# KS0108_2Wire.net
KiCad netlist of a schematic drawn in EAGLE
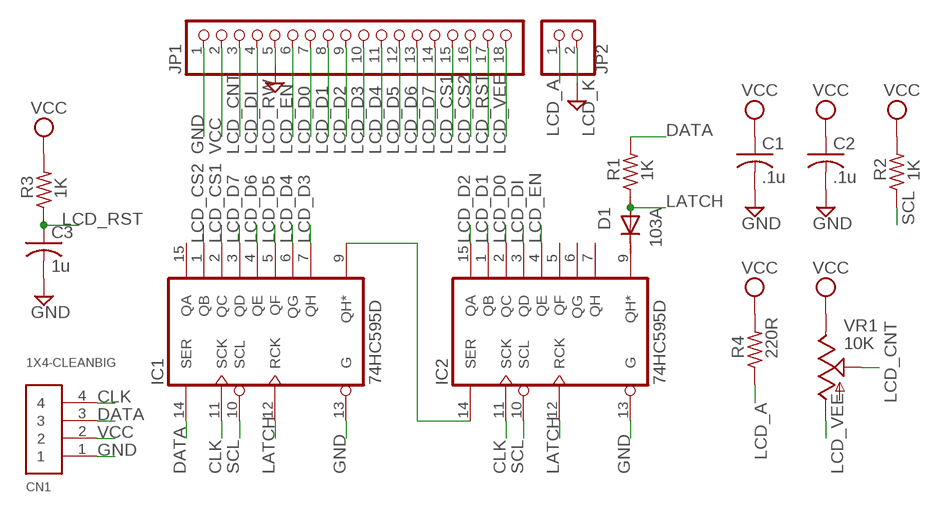
[diagram p0: schematic, sheet 1]

(export (version "E")
  (design (tool "Eeschema 10.0.6"))
  (components
    (comp (ref "C1")
      (value ".1u")
      (footprint "eagle-import:C1206")
      (libsource (lib "eagle-import") (part "C-USC1206"))
    )
    (comp (ref "C2")
      (value ".1u")
      (footprint "eagle-import:C1206")
      (libsource (lib "eagle-import") (part "C-USC1206"))
    )
    (comp (ref "C3")
      (value "1u")
      (footprint "eagle-import:C1206")
      (libsource (lib "eagle-import") (part "C-USC1206"))
    )
    (comp (ref "CN1")
      (value "1X4-CLEANBIG")
      (footprint "eagle-import:1X04-CLEANBIG")
      (libsource (lib "eagle-import") (part "1X4-CLEANBIG"))
    )
    (comp (ref "D1")
      (value "103A")
      (footprint "eagle-import:SOD80C")
      (libsource (lib "eagle-import") (part "DIODE-SOD80C"))
    )
    (comp (ref "IC1")
      (value "74HC595D")
      (footprint "eagle-import:SO16")
      (libsource (lib "eagle-import") (part "74595DHC"))
    )
    (comp (ref "IC2")
      (value "74HC595D")
      (footprint "eagle-import:SO16")
      (libsource (lib "eagle-import") (part "74595DHC"))
    )
    (comp (ref "JP1")
      (value "PINHD-1X18-BIG")
      (footprint "eagle-import:1X18-BIG")
      (libsource (lib "eagle-import") (part "PINHD-1X18-BIG"))
    )
    (comp (ref "JP2")
      (value "HEADER-1X2ROUND")
      (footprint "eagle-import:1X02_ROUND")
      (libsource (lib "eagle-import") (part "HEADER-1X2ROUND"))
    )
    (comp (ref "R1")
      (value "1K")
      (footprint "eagle-import:R1206")
      (libsource (lib "eagle-import") (part "R-US_R1206"))
    )
    (comp (ref "R2")
      (value "1K")
      (footprint "eagle-import:R1206")
      (libsource (lib "eagle-import") (part "R-US_R1206"))
    )
    (comp (ref "R3")
      (value "1K")
      (footprint "eagle-import:R1206")
      (libsource (lib "eagle-import") (part "R-US_R1206"))
    )
    (comp (ref "R4")
      (value "220R")
      (footprint "eagle-import:R1206")
      (libsource (lib "eagle-import") (part "R-US_R1206"))
    )
    (comp (ref "VR1")
      (value "10K")
      (footprint "eagle-import:CT6")
      (libsource (lib "eagle-import") (part "TRIM_US-CT6"))
    )
  )
  (nets
    (net (code "1") (name "/CLK") (class "Default")
      (node (ref "CN1") (pin "4") (pinfunction "4_4") (pintype "bidirectional"))
      (node (ref "IC1") (pin "11") (pinfunction "SCK_11") (pintype "input"))
      (node (ref "IC2") (pin "11") (pinfunction "SCK_11") (pintype "input"))
    )
    (net (code "2") (name "/DATA") (class "Default")
      (node (ref "CN1") (pin "3") (pinfunction "3_3") (pintype "bidirectional"))
      (node (ref "IC1") (pin "14") (pinfunction "SER_14") (pintype "input"))
      (node (ref "R1") (pin "2") (pinfunction "2_2") (pintype "passive"))
    )
    (net (code "3") (name "/LATCH") (class "Default")
      (node (ref "D1") (pin "A") (pinfunction "A_A") (pintype "passive"))
      (node (ref "IC1") (pin "12") (pinfunction "RCK_12") (pintype "input"))
      (node (ref "IC2") (pin "12") (pinfunction "RCK_12") (pintype "input"))
      (node (ref "R1") (pin "1") (pinfunction "1_1") (pintype "passive"))
    )
    (net (code "4") (name "/LCD_A") (class "Default")
      (node (ref "JP2") (pin "1") (pinfunction "1_1") (pintype "passive"))
      (node (ref "R4") (pin "1") (pinfunction "1_1") (pintype "passive"))
    )
    (net (code "5") (name "/LCD_CNT") (class "Default")
      (node (ref "JP1") (pin "3") (pinfunction "3_3") (pintype "passive"))
      (node (ref "VR1") (pin "S") (pinfunction "S_S") (pintype "passive"))
    )
    (net (code "6") (name "/LCD_CS1") (class "Default")
      (node (ref "IC1") (pin "2") (pinfunction "QC_2") (pintype "tri_state"))
      (node (ref "JP1") (pin "15") (pinfunction "15_15") (pintype "passive"))
    )
    (net (code "7") (name "/LCD_CS2") (class "Default")
      (node (ref "IC1") (pin "1") (pinfunction "QB_1") (pintype "tri_state"))
      (node (ref "JP1") (pin "16") (pinfunction "16_16") (pintype "passive"))
    )
    (net (code "8") (name "/LCD_D0") (class "Default")
      (node (ref "IC2") (pin "2") (pinfunction "QC_2") (pintype "tri_state"))
      (node (ref "JP1") (pin "7") (pinfunction "7_7") (pintype "passive"))
    )
    (net (code "9") (name "/LCD_D1") (class "Default")
      (node (ref "IC2") (pin "1") (pinfunction "QB_1") (pintype "tri_state"))
      (node (ref "JP1") (pin "8") (pinfunction "8_8") (pintype "passive"))
    )
    (net (code "10") (name "/LCD_D2") (class "Default")
      (node (ref "IC2") (pin "15") (pinfunction "QA_15") (pintype "tri_state"))
      (node (ref "JP1") (pin "9") (pinfunction "9_9") (pintype "passive"))
    )
    (net (code "11") (name "/LCD_D3") (class "Default")
      (node (ref "IC1") (pin "7") (pinfunction "QH_7") (pintype "tri_state"))
      (node (ref "JP1") (pin "10") (pinfunction "10_10") (pintype "passive"))
    )
    (net (code "12") (name "/LCD_D4") (class "Default")
      (node (ref "IC1") (pin "6") (pinfunction "QG_6") (pintype "tri_state"))
      (node (ref "JP1") (pin "11") (pinfunction "11_11") (pintype "passive"))
    )
    (net (code "13") (name "/LCD_D5") (class "Default")
      (node (ref "IC1") (pin "5") (pinfunction "QF_5") (pintype "tri_state"))
      (node (ref "JP1") (pin "12") (pinfunction "12_12") (pintype "passive"))
    )
    (net (code "14") (name "/LCD_D6") (class "Default")
      (node (ref "IC1") (pin "4") (pinfunction "QE_4") (pintype "tri_state"))
      (node (ref "JP1") (pin "13") (pinfunction "13_13") (pintype "passive"))
    )
    (net (code "15") (name "/LCD_D7") (class "Default")
      (node (ref "IC1") (pin "3") (pinfunction "QD_3") (pintype "tri_state"))
      (node (ref "JP1") (pin "14") (pinfunction "14_14") (pintype "passive"))
    )
    (net (code "16") (name "/LCD_DI") (class "Default")
      (node (ref "IC2") (pin "3") (pinfunction "QD_3") (pintype "tri_state"))
      (node (ref "JP1") (pin "4") (pinfunction "4_4") (pintype "passive"))
    )
    (net (code "17") (name "/LCD_EN") (class "Default")
      (node (ref "IC2") (pin "4") (pinfunction "QE_4") (pintype "tri_state"))
      (node (ref "JP1") (pin "6") (pinfunction "6_6") (pintype "passive"))
    )
    (net (code "18") (name "/LCD_RST") (class "Default")
      (node (ref "C3") (pin "1") (pinfunction "1_1") (pintype "passive"))
      (node (ref "JP1") (pin "17") (pinfunction "17_17") (pintype "passive"))
      (node (ref "R3") (pin "1") (pinfunction "1_1") (pintype "passive"))
    )
    (net (code "19") (name "/LCD_VEE") (class "Default")
      (node (ref "JP1") (pin "18") (pinfunction "18_18") (pintype "passive"))
      (node (ref "VR1") (pin "A") (pinfunction "A_A") (pintype "passive"))
    )
    (net (code "20") (name "/SCL") (class "Default")
      (node (ref "IC1") (pin "10") (pinfunction "SCL_10") (pintype "input"))
      (node (ref "IC2") (pin "10") (pinfunction "SCL_10") (pintype "input"))
      (node (ref "R2") (pin "1") (pinfunction "1_1") (pintype "passive"))
    )
    (net (code "21") (name "GND") (class "Default")
      (node (ref "C1") (pin "2") (pinfunction "2_2") (pintype "passive"))
      (node (ref "C2") (pin "2") (pinfunction "2_2") (pintype "passive"))
      (node (ref "C3") (pin "2") (pinfunction "2_2") (pintype "passive"))
      (node (ref "CN1") (pin "1") (pinfunction "1_1") (pintype "bidirectional"))
      (node (ref "IC1") (pin "13") (pinfunction "G_13") (pintype "input"))
      (node (ref "IC2") (pin "13") (pinfunction "G_13") (pintype "input"))
      (node (ref "JP1") (pin "1") (pinfunction "1_1") (pintype "passive"))
      (node (ref "JP1") (pin "5") (pinfunction "5_5") (pintype "passive"))
      (node (ref "JP2") (pin "2") (pinfunction "2_2") (pintype "passive"))
    )
    (net (code "22") (name "Net-(IC1A-QH*)") (class "Default")
      (node (ref "IC1") (pin "9") (pinfunction "QH*_9") (pintype "tri_state"))
      (node (ref "IC2") (pin "14") (pinfunction "SER_14") (pintype "input"))
    )
    (net (code "23") (name "Net-(IC2A-QH*)") (class "Default")
      (node (ref "D1") (pin "C") (pinfunction "C_C") (pintype "passive"))
      (node (ref "IC2") (pin "9") (pinfunction "QH*_9") (pintype "tri_state"))
    )
    (net (code "24") (name "VCC") (class "Default")
      (node (ref "C1") (pin "1") (pinfunction "1_1") (pintype "passive"))
      (node (ref "C2") (pin "1") (pinfunction "1_1") (pintype "passive"))
      (node (ref "CN1") (pin "2") (pinfunction "2_2") (pintype "bidirectional"))
      (node (ref "JP1") (pin "2") (pinfunction "2_2") (pintype "passive"))
      (node (ref "R2") (pin "2") (pinfunction "2_2") (pintype "passive"))
      (node (ref "R3") (pin "2") (pinfunction "2_2") (pintype "passive"))
      (node (ref "R4") (pin "2") (pinfunction "2_2") (pintype "passive"))
      (node (ref "VR1") (pin "E") (pinfunction "E_E") (pintype "passive"))
    )
    (net (code "25") (name "unconnected-(IC1A-QA-Pad15)") (class "Default")
      (node (ref "IC1") (pin "15") (pinfunction "QA_15") (pintype "tri_state"))
    )
    (net (code "26") (name "unconnected-(IC2A-QF-Pad5)") (class "Default")
      (node (ref "IC2") (pin "5") (pinfunction "QF_5") (pintype "tri_state"))
    )
    (net (code "27") (name "unconnected-(IC2A-QG-Pad6)") (class "Default")
      (node (ref "IC2") (pin "6") (pinfunction "QG_6") (pintype "tri_state"))
    )
    (net (code "28") (name "unconnected-(IC2A-QH-Pad7)") (class "Default")
      (node (ref "IC2") (pin "7") (pinfunction "QH_7") (pintype "tri_state"))
    )
  )
)
